# DAC_8CH.net
KiCad netlist of a schematic drawn in Altium Designer
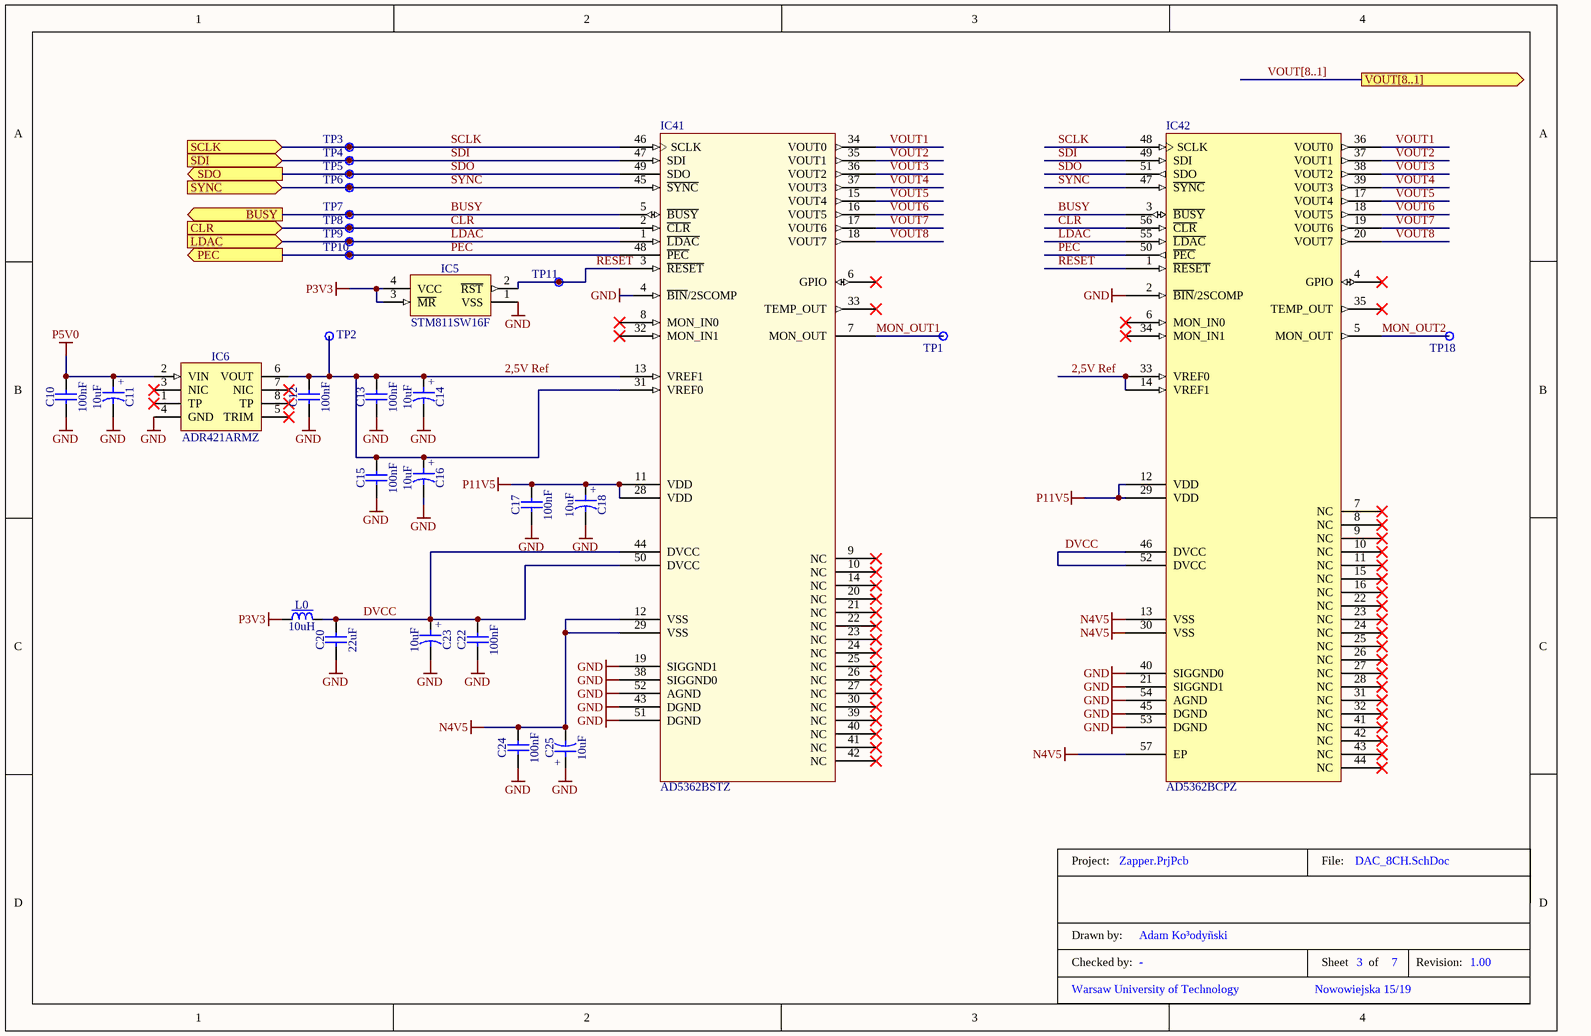
[diagram p0: DAC_8CH.SchDoc]

(export (version "E")
  (design (tool "Eeschema 10.0.6"))
  (components
    (comp (ref "C10")
      (value "100nF")
      (footprint "CAPC1005X55N")
      (description "Non-polarised capacitor")
      (fields
        (field (name "PART NUMBER") "CC0402_100NF_16V_10%_X7R")
        (field (name "VOLTAGE") "16V")
        (field (name "AUTHOR") "CERN DEM JLC")
      )
      (libsource (lib "Capacitors") (part "Capacitor - non polarized"))
    )
    (comp (ref "C11")
      (value "10uF")
      (footprint "CAPMP3528X210N")
      (description "Polarised capacitor")
      (fields
        (field (name "PART NUMBER") "CTE3528-21_10UF_16V_20%_PANASONIC_TQC")
        (field (name "VOLTAGE") "16V")
        (field (name "AUTHOR") "CERN DEM JLC")
      )
      (libsource (lib "Capacitors") (part "Capacitor - polarized"))
    )
    (comp (ref "C12")
      (value "100nF")
      (footprint "CAPC1005X55N")
      (description "Non-polarised capacitor")
      (fields
        (field (name "PART NUMBER") "CC0402_100NF_16V_10%_X7R")
        (field (name "VOLTAGE") "16V")
        (field (name "AUTHOR") "CERN DEM JLC")
      )
      (libsource (lib "Capacitors") (part "Capacitor - non polarized"))
    )
    (comp (ref "C13")
      (value "100nF")
      (footprint "CAPC1005X55N")
      (description "Non-polarised capacitor")
      (fields
        (field (name "PART NUMBER") "CC0402_100NF_16V_10%_X7R")
        (field (name "VOLTAGE") "16V")
        (field (name "AUTHOR") "CERN DEM JLC")
      )
      (libsource (lib "Capacitors") (part "Capacitor - non polarized"))
    )
    (comp (ref "C14")
      (value "10uF")
      (footprint "CAPMP3528X210N")
      (description "Polarised capacitor")
      (fields
        (field (name "PART NUMBER") "CTE3528-21_10UF_16V_20%_PANASONIC_TQC")
        (field (name "VOLTAGE") "16V")
        (field (name "AUTHOR") "CERN DEM JLC")
      )
      (libsource (lib "Capacitors") (part "Capacitor - polarized"))
    )
    (comp (ref "C15")
      (value "100nF")
      (footprint "CAPC1005X55N")
      (description "Non-polarised capacitor")
      (fields
        (field (name "PART NUMBER") "CC0402_100NF_16V_10%_X7R")
        (field (name "VOLTAGE") "16V")
        (field (name "AUTHOR") "CERN DEM JLC")
      )
      (libsource (lib "Capacitors") (part "Capacitor - non polarized"))
    )
    (comp (ref "C16")
      (value "10uF")
      (footprint "CAPMP3528X210N")
      (description "Polarised capacitor")
      (fields
        (field (name "PART NUMBER") "CTE3528-21_10UF_16V_20%_PANASONIC_TQC")
        (field (name "VOLTAGE") "16V")
        (field (name "AUTHOR") "CERN DEM JLC")
      )
      (libsource (lib "Capacitors") (part "Capacitor - polarized"))
    )
    (comp (ref "C17")
      (value "100nF")
      (footprint "CAPC1005X55N")
      (description "Non-polarised capacitor")
      (fields
        (field (name "PART NUMBER") "CC0402_100NF_16V_10%_X7R")
        (field (name "VOLTAGE") "16V")
        (field (name "AUTHOR") "CERN DEM JLC")
      )
      (libsource (lib "Capacitors") (part "Capacitor - non polarized"))
    )
    (comp (ref "C18")
      (value "10uF")
      (footprint "CAPMP3528X210N")
      (description "Polarised capacitor")
      (fields
        (field (name "PART NUMBER") "CTE3528-21_10UF_16V_20%_PANASONIC_TQC")
        (field (name "VOLTAGE") "16V")
        (field (name "AUTHOR") "CERN DEM JLC")
      )
      (libsource (lib "Capacitors") (part "Capacitor - polarized"))
    )
    (comp (ref "C20")
      (value "22uF")
      (footprint "CAPC2012X135N")
      (description "Non-polarised capacitor")
      (fields
        (field (name "PART NUMBER") "CC0805_22UF_16V_10%_X5R")
        (field (name "VOLTAGE") "16V")
        (field (name "AUTHOR") "CERN DEM JLC")
      )
      (libsource (lib "Capacitors") (part "Capacitor - non polarized"))
    )
    (comp (ref "C22")
      (value "100nF")
      (footprint "CAPC1005X55N")
      (description "Non-polarised capacitor")
      (fields
        (field (name "PART NUMBER") "CC0402_100NF_16V_10%_X7R")
        (field (name "VOLTAGE") "16V")
        (field (name "AUTHOR") "CERN DEM JLC")
      )
      (libsource (lib "Capacitors") (part "Capacitor - non polarized"))
    )
    (comp (ref "C23")
      (value "10uF")
      (footprint "CAPMP3528X210N")
      (description "Polarised capacitor")
      (fields
        (field (name "PART NUMBER") "CTE3528-21_10UF_16V_20%_PANASONIC_TQC")
        (field (name "VOLTAGE") "16V")
        (field (name "AUTHOR") "CERN DEM JLC")
      )
      (libsource (lib "Capacitors") (part "Capacitor - polarized"))
    )
    (comp (ref "C24")
      (value "100nF")
      (footprint "CAPC1005X55N")
      (description "Non-polarised capacitor")
      (fields
        (field (name "PART NUMBER") "CC0402_100NF_16V_10%_X7R")
        (field (name "VOLTAGE") "16V")
        (field (name "AUTHOR") "CERN DEM JLC")
      )
      (libsource (lib "Capacitors") (part "Capacitor - non polarized"))
    )
    (comp (ref "C25")
      (value "10uF")
      (footprint "CAPMP3528X210N")
      (description "Polarised capacitor")
      (fields
        (field (name "PART NUMBER") "CTE3528-21_10UF_16V_20%_PANASONIC_TQC")
        (field (name "VOLTAGE") "16V")
        (field (name "AUTHOR") "CERN DEM JLC")
      )
      (libsource (lib "Capacitors") (part "Capacitor - polarized"))
    )
    (comp (ref "IC5")
      (value "STM811SW16F")
      (footprint "SOT143N")
      (description "Microprocessor Reset Circuit")
      (fields (field (name "MANUFACTURER") "ST MICROELECTRONICS") (field (name "AUTHOR") "CERN DEM JLC"))
      (libsource (lib "ICs And Semiconductors") (part "STM811"))
    )
    (comp (ref "IC6")
      (value "ADR421ARMZ")
      (footprint "SOP65P490X110-8N")
      (description "Ultraprecision, Low Noise, 2.048 V/2.500 V/  3.00 V/5.00 V XFET Voltage References")
      (fields (field (name "MANUFACTURER") "ANALOG DEVICES") (field (name "AUTHOR") "CERN DEM JLC"))
      (libsource (lib "ICs And Semiconductors") (part "ADR42x"))
    )
    (comp (ref "IC41")
      (value "AD5362BSTZ")
      (footprint "ST-52_N")
      (description "IC, 16BIT DAC, 8CH, SERIAL, 52LFCSP")
      (libsource (lib "InzLib") (part "AD5362BSTZ"))
    )
    (comp (ref "IC42")
      (value "AD5362BCPZ")
      (footprint "CP-56-1_N")
      (description "DAC 8-CH Resistor-String 16-bit 56-Pin LFCSP EP Tray")
      (libsource (lib "InzLib") (part "AD5362BCPZ"))
    )
    (comp (ref "L0")
      (value "10uH")
      (footprint "IND_MURATA-PS_8400")
      (description "Inductor With Core")
      (fields
        (field (name "PART NUMBER") "IND_10UH_10%_MURATA-PS_8400")
        (field (name "POWER") "950mA")
        (field (name "AUTHOR") "CERN DEM JLC")
      )
      (libsource (lib "Inductors & Transformers") (part "Inductor With Magnetic core"))
    )
    (comp (ref "TitleBlock3") (value "TitleBlock") (libsource (lib "InzLib") (part "TitleBlock")))
    (comp (ref "TP1")
      (value "Test Point")
      (footprint "TPS127")
      (fields (field (name "PART NUMBER") "SMD_PAD_1.27X1.27MM") (field (name "AUTHOR") "CERN DEM JLC"))
      (libsource (lib "Eletro-mechanical") (part "Test Point"))
    )
    (comp (ref "TP2")
      (value "Test Point")
      (footprint "TPS127")
      (fields (field (name "PART NUMBER") "SMD_PAD_1.27X1.27MM") (field (name "AUTHOR") "CERN DEM JLC"))
      (libsource (lib "Eletro-mechanical") (part "Test Point"))
    )
    (comp (ref "TP3")
      (value "Test Point")
      (footprint "TPS127")
      (fields (field (name "PART NUMBER") "SMD_PAD_1.27X1.27MM") (field (name "AUTHOR") "CERN DEM JLC"))
      (libsource (lib "Eletro-mechanical") (part "Test Point"))
    )
    (comp (ref "TP4")
      (value "Test Point")
      (footprint "TPS127")
      (fields (field (name "PART NUMBER") "SMD_PAD_1.27X1.27MM") (field (name "AUTHOR") "CERN DEM JLC"))
      (libsource (lib "Eletro-mechanical") (part "Test Point"))
    )
    (comp (ref "TP5")
      (value "Test Point")
      (footprint "TPS127")
      (fields (field (name "PART NUMBER") "SMD_PAD_1.27X1.27MM") (field (name "AUTHOR") "CERN DEM JLC"))
      (libsource (lib "Eletro-mechanical") (part "Test Point"))
    )
    (comp (ref "TP6")
      (value "Test Point")
      (footprint "TPS127")
      (fields (field (name "PART NUMBER") "SMD_PAD_1.27X1.27MM") (field (name "AUTHOR") "CERN DEM JLC"))
      (libsource (lib "Eletro-mechanical") (part "Test Point"))
    )
    (comp (ref "TP7")
      (value "Test Point")
      (footprint "TPS127")
      (fields (field (name "PART NUMBER") "SMD_PAD_1.27X1.27MM") (field (name "AUTHOR") "CERN DEM JLC"))
      (libsource (lib "Eletro-mechanical") (part "Test Point"))
    )
    (comp (ref "TP8")
      (value "Test Point")
      (footprint "TPS127")
      (fields (field (name "PART NUMBER") "SMD_PAD_1.27X1.27MM") (field (name "AUTHOR") "CERN DEM JLC"))
      (libsource (lib "Eletro-mechanical") (part "Test Point"))
    )
    (comp (ref "TP9")
      (value "Test Point")
      (footprint "TPS127")
      (fields (field (name "PART NUMBER") "SMD_PAD_1.27X1.27MM") (field (name "AUTHOR") "CERN DEM JLC"))
      (libsource (lib "Eletro-mechanical") (part "Test Point"))
    )
    (comp (ref "TP10")
      (value "Test Point")
      (footprint "TPS127")
      (fields (field (name "PART NUMBER") "SMD_PAD_1.27X1.27MM") (field (name "AUTHOR") "CERN DEM JLC"))
      (libsource (lib "Eletro-mechanical") (part "Test Point"))
    )
    (comp (ref "TP11")
      (value "Test Point")
      (footprint "TPS127")
      (fields (field (name "PART NUMBER") "SMD_PAD_1.27X1.27MM") (field (name "AUTHOR") "CERN DEM JLC"))
      (libsource (lib "Eletro-mechanical") (part "Test Point"))
    )
    (comp (ref "TP18")
      (value "Test Point")
      (footprint "TPS127")
      (fields (field (name "PART NUMBER") "SMD_PAD_1.27X1.27MM") (field (name "AUTHOR") "CERN DEM JLC"))
      (libsource (lib "Eletro-mechanical") (part "Test Point"))
    )
  )
  (nets
    (net (code "1") (name "/2,5V Ref") (class "Default")
      (node (ref "C12") (pin "2") (pinfunction "2_2") (pintype "passive"))
      (node (ref "C13") (pin "2") (pinfunction "2_2") (pintype "passive"))
      (node (ref "C14") (pin "1") (pinfunction "1_1") (pintype "passive"))
      (node (ref "C15") (pin "2") (pinfunction "2_2") (pintype "passive"))
      (node (ref "C16") (pin "1") (pinfunction "1_1") (pintype "passive"))
      (node (ref "IC41") (pin "13") (pinfunction "VREF1_13") (pintype "input"))
      (node (ref "IC41") (pin "31") (pinfunction "VREF0_31") (pintype "input"))
      (node (ref "IC42") (pin "14") (pinfunction "VREF1_14") (pintype "input"))
      (node (ref "IC42") (pin "33") (pinfunction "VREF0_33") (pintype "input"))
      (node (ref "IC6") (pin "6") (pinfunction "VOUT_6") (pintype "power_in"))
      (node (ref "TP2") (pin "1") (pinfunction "1_1") (pintype "bidirectional"))
    )
    (net (code "2") (name "/BUSY") (class "Default")
      (node (ref "IC41") (pin "5") (pinfunction "~{BUSY}_5") (pintype "bidirectional"))
      (node (ref "IC42") (pin "3") (pinfunction "~{BUSY}_3") (pintype "bidirectional"))
      (node (ref "TP7") (pin "1") (pinfunction "1_1") (pintype "bidirectional"))
    )
    (net (code "3") (name "/CLR") (class "Default")
      (node (ref "IC41") (pin "2") (pinfunction "~{CLR}_2") (pintype "input"))
      (node (ref "IC42") (pin "56") (pinfunction "~{CLR}_56") (pintype "input"))
      (node (ref "TP8") (pin "1") (pinfunction "1_1") (pintype "bidirectional"))
    )
    (net (code "4") (name "/DVCC") (class "Default")
      (node (ref "C20") (pin "2") (pinfunction "2_2") (pintype "passive"))
      (node (ref "C22") (pin "2") (pinfunction "2_2") (pintype "passive"))
      (node (ref "C23") (pin "1") (pinfunction "1_1") (pintype "passive"))
      (node (ref "IC41") (pin "44") (pinfunction "DVCC_44") (pintype "power_in"))
      (node (ref "IC41") (pin "50") (pinfunction "DVCC_50") (pintype "power_in"))
      (node (ref "IC42") (pin "46") (pinfunction "DVCC_46") (pintype "passive"))
      (node (ref "IC42") (pin "52") (pinfunction "DVCC_52") (pintype "passive"))
      (node (ref "L0") (pin "2") (pinfunction "2_2") (pintype "passive"))
    )
    (net (code "5") (name "/LDAC") (class "Default")
      (node (ref "IC41") (pin "1") (pinfunction "~{LDAC}_1") (pintype "input"))
      (node (ref "IC42") (pin "55") (pinfunction "~{LDAC}_55") (pintype "input"))
      (node (ref "TP9") (pin "1") (pinfunction "1_1") (pintype "bidirectional"))
    )
    (net (code "6") (name "/MON_OUT1") (class "Default")
      (node (ref "IC41") (pin "7") (pinfunction "MON_OUT_7") (pintype "tri_state"))
      (node (ref "TP1") (pin "1") (pinfunction "1_1") (pintype "bidirectional"))
    )
    (net (code "7") (name "/MON_OUT2") (class "Default")
      (node (ref "IC42") (pin "5") (pinfunction "MON_OUT_5") (pintype "output"))
      (node (ref "TP18") (pin "1") (pinfunction "1_1") (pintype "bidirectional"))
    )
    (net (code "8") (name "/PEC") (class "Default")
      (node (ref "IC41") (pin "48") (pinfunction "~{PEC}_48") (pintype "open_collector"))
      (node (ref "IC42") (pin "50") (pinfunction "~{PEC}_50") (pintype "output"))
      (node (ref "TP10") (pin "1") (pinfunction "1_1") (pintype "bidirectional"))
    )
    (net (code "9") (name "/SCLK") (class "Default")
      (node (ref "IC41") (pin "46") (pinfunction "SCLK_46") (pintype "input"))
      (node (ref "IC42") (pin "48") (pinfunction "SCLK_48") (pintype "input"))
      (node (ref "TP3") (pin "1") (pinfunction "1_1") (pintype "bidirectional"))
    )
    (net (code "10") (name "/SDI") (class "Default")
      (node (ref "IC41") (pin "47") (pinfunction "SDI_47") (pintype "input"))
      (node (ref "IC42") (pin "49") (pinfunction "SDI_49") (pintype "input"))
      (node (ref "TP4") (pin "1") (pinfunction "1_1") (pintype "bidirectional"))
    )
    (net (code "11") (name "/SDO") (class "Default")
      (node (ref "IC41") (pin "49") (pinfunction "SDO_49") (pintype "tri_state"))
      (node (ref "IC42") (pin "51") (pinfunction "SDO_51") (pintype "output"))
      (node (ref "TP5") (pin "1") (pinfunction "1_1") (pintype "bidirectional"))
    )
    (net (code "12") (name "/SYNC") (class "Default")
      (node (ref "IC41") (pin "45") (pinfunction "~{SYNC}_45") (pintype "input"))
      (node (ref "IC42") (pin "47") (pinfunction "~{SYNC}_47") (pintype "input"))
      (node (ref "TP6") (pin "1") (pinfunction "1_1") (pintype "bidirectional"))
    )
    (net (code "13") (name "/VOUT1") (class "Default")
      (node (ref "IC41") (pin "34") (pinfunction "VOUT0_34") (pintype "output"))
      (node (ref "IC42") (pin "36") (pinfunction "VOUT0_36") (pintype "output"))
    )
    (net (code "14") (name "/VOUT2") (class "Default")
      (node (ref "IC41") (pin "35") (pinfunction "VOUT1_35") (pintype "output"))
      (node (ref "IC42") (pin "37") (pinfunction "VOUT1_37") (pintype "output"))
    )
    (net (code "15") (name "/VOUT3") (class "Default")
      (node (ref "IC41") (pin "36") (pinfunction "VOUT2_36") (pintype "output"))
      (node (ref "IC42") (pin "38") (pinfunction "VOUT2_38") (pintype "output"))
    )
    (net (code "16") (name "/VOUT4") (class "Default")
      (node (ref "IC41") (pin "37") (pinfunction "VOUT3_37") (pintype "output"))
      (node (ref "IC42") (pin "39") (pinfunction "VOUT3_39") (pintype "output"))
    )
    (net (code "17") (name "/VOUT5") (class "Default")
      (node (ref "IC41") (pin "15") (pinfunction "VOUT4_15") (pintype "output"))
      (node (ref "IC42") (pin "17") (pinfunction "VOUT4_17") (pintype "output"))
    )
    (net (code "18") (name "/VOUT6") (class "Default")
      (node (ref "IC41") (pin "16") (pinfunction "VOUT5_16") (pintype "output"))
      (node (ref "IC42") (pin "18") (pinfunction "VOUT5_18") (pintype "output"))
    )
    (net (code "19") (name "/VOUT7") (class "Default")
      (node (ref "IC41") (pin "17") (pinfunction "VOUT6_17") (pintype "output"))
      (node (ref "IC42") (pin "19") (pinfunction "VOUT6_19") (pintype "output"))
    )
    (net (code "20") (name "/VOUT8") (class "Default")
      (node (ref "IC41") (pin "18") (pinfunction "VOUT7_18") (pintype "output"))
      (node (ref "IC42") (pin "20") (pinfunction "VOUT7_20") (pintype "output"))
    )
    (net (code "22") (name "/~{RESET}") (class "Default")
      (node (ref "IC41") (pin "3") (pinfunction "~{RESET}_3") (pintype "input"))
      (node (ref "IC42") (pin "1") (pinfunction "~{RESET}_1") (pintype "input"))
      (node (ref "IC5") (pin "2") (pinfunction "~{RST}_2") (pintype "output"))
      (node (ref "TP11") (pin "1") (pinfunction "1_1") (pintype "bidirectional"))
    )
    (net (code "23") (name "GND") (class "Default")
      (node (ref "C10") (pin "1") (pinfunction "1_1") (pintype "passive"))
      (node (ref "C11") (pin "2") (pinfunction "2_2") (pintype "passive"))
      (node (ref "C12") (pin "1") (pinfunction "1_1") (pintype "passive"))
      (node (ref "C13") (pin "1") (pinfunction "1_1") (pintype "passive"))
      (node (ref "C14") (pin "2") (pinfunction "2_2") (pintype "passive"))
      (node (ref "C15") (pin "1") (pinfunction "1_1") (pintype "passive"))
      (node (ref "C16") (pin "2") (pinfunction "2_2") (pintype "passive"))
      (node (ref "C17") (pin "1") (pinfunction "1_1") (pintype "passive"))
      (node (ref "C18") (pin "2") (pinfunction "2_2") (pintype "passive"))
      (node (ref "C20") (pin "1") (pinfunction "1_1") (pintype "passive"))
      (node (ref "C22") (pin "1") (pinfunction "1_1") (pintype "passive"))
      (node (ref "C23") (pin "2") (pinfunction "2_2") (pintype "passive"))
      (node (ref "C24") (pin "1") (pinfunction "1_1") (pintype "passive"))
      (node (ref "C25") (pin "1") (pinfunction "1_1") (pintype "passive"))
      (node (ref "IC41") (pin "19") (pinfunction "SIGGND1_19") (pintype "power_in"))
      (node (ref "IC41") (pin "38") (pinfunction "SIGGND0_38") (pintype "power_in"))
      (node (ref "IC41") (pin "4") (pinfunction "~{BIN}/2SCOMP_4") (pintype "input"))
      (node (ref "IC41") (pin "43") (pinfunction "DGND_43") (pintype "power_in"))
      (node (ref "IC41") (pin "51") (pinfunction "DGND_51") (pintype "power_in"))
      (node (ref "IC41") (pin "52") (pinfunction "AGND_52") (pintype "power_in"))
      (node (ref "IC42") (pin "2") (pinfunction "~{BIN}/2SCOMP_2") (pintype "input"))
      (node (ref "IC42") (pin "21") (pinfunction "SIGGND1_21") (pintype "passive"))
      (node (ref "IC42") (pin "40") (pinfunction "SIGGND0_40") (pintype "passive"))
      (node (ref "IC42") (pin "45") (pinfunction "DGND_45") (pintype "passive"))
      (node (ref "IC42") (pin "53") (pinfunction "DGND_53") (pintype "passive"))
      (node (ref "IC42") (pin "54") (pinfunction "AGND_54") (pintype "passive"))
      (node (ref "IC5") (pin "1") (pinfunction "VSS_1") (pintype "power_in"))
      (node (ref "IC6") (pin "4") (pinfunction "GND_4") (pintype "power_in"))
    )
    (net (code "24") (name "N4V5") (class "Default")
      (node (ref "C24") (pin "2") (pinfunction "2_2") (pintype "passive"))
      (node (ref "C25") (pin "2") (pinfunction "2_2") (pintype "passive"))
      (node (ref "IC41") (pin "12") (pinfunction "VSS_12") (pintype "power_in"))
      (node (ref "IC41") (pin "29") (pinfunction "VSS_29") (pintype "power_in"))
      (node (ref "IC42") (pin "13") (pinfunction "VSS_13") (pintype "passive"))
      (node (ref "IC42") (pin "30") (pinfunction "VSS_30") (pintype "passive"))
      (node (ref "IC42") (pin "57") (pinfunction "EP_57") (pintype "passive"))
    )
    (net (code "25") (name "P3V3") (class "Default")
      (node (ref "IC5") (pin "3") (pinfunction "~{MR}_3") (pintype "input"))
      (node (ref "IC5") (pin "4") (pinfunction "VCC_4") (pintype "power_in"))
      (node (ref "L0") (pin "1") (pinfunction "1_1") (pintype "passive"))
    )
    (net (code "26") (name "P5V0") (class "Default")
      (node (ref "C10") (pin "2") (pinfunction "2_2") (pintype "passive"))
      (node (ref "C11") (pin "1") (pinfunction "1_1") (pintype "passive"))
      (node (ref "IC6") (pin "2") (pinfunction "VIN_2") (pintype "input"))
    )
    (net (code "27") (name "P11V5") (class "Default")
      (node (ref "C17") (pin "2") (pinfunction "2_2") (pintype "passive"))
      (node (ref "C18") (pin "1") (pinfunction "1_1") (pintype "passive"))
      (node (ref "IC41") (pin "11") (pinfunction "VDD_11") (pintype "power_in"))
      (node (ref "IC41") (pin "28") (pinfunction "VDD_28") (pintype "power_in"))
      (node (ref "IC42") (pin "12") (pinfunction "VDD_12") (pintype "passive"))
      (node (ref "IC42") (pin "29") (pinfunction "VDD_29") (pintype "passive"))
    )
    (net (code "28") (name "unconnected-(IC6-NIC-Pad3)") (class "Default")
      (node (ref "IC6") (pin "3") (pinfunction "NIC_3") (pintype "passive+no_connect"))
    )
    (net (code "29") (name "unconnected-(IC6-NIC-Pad7)") (class "Default")
      (node (ref "IC6") (pin "7") (pinfunction "NIC_7") (pintype "passive+no_connect"))
    )
    (net (code "30") (name "unconnected-(IC6-TP-Pad1)") (class "Default")
      (node (ref "IC6") (pin "1") (pinfunction "TP_1") (pintype "passive+no_connect"))
    )
    (net (code "31") (name "unconnected-(IC6-TP-Pad8)") (class "Default")
      (node (ref "IC6") (pin "8") (pinfunction "TP_8") (pintype "passive+no_connect"))
    )
    (net (code "32") (name "unconnected-(IC6-TRIM-Pad5)") (class "Default")
      (node (ref "IC6") (pin "5") (pinfunction "TRIM_5") (pintype "passive+no_connect"))
    )
    (net (code "33") (name "unconnected-(IC41-GPIO-Pad6)") (class "Default")
      (node (ref "IC41") (pin "6") (pinfunction "GPIO_6") (pintype "bidirectional+no_connect"))
    )
    (net (code "34") (name "unconnected-(IC41-MON_IN0-Pad8)") (class "Default")
      (node (ref "IC41") (pin "8") (pinfunction "MON_IN0_8") (pintype "input+no_connect"))
    )
    (net (code "35") (name "unconnected-(IC41-MON_IN1-Pad32)") (class "Default")
      (node (ref "IC41") (pin "32") (pinfunction "MON_IN1_32") (pintype "input+no_connect"))
    )
    (net (code "36") (name "unconnected-(IC41-NC-Pad9)") (class "Default")
      (node (ref "IC41") (pin "9") (pinfunction "NC_9") (pintype "passive+no_connect"))
    )
    (net (code "37") (name "unconnected-(IC41-NC-Pad10)") (class "Default")
      (node (ref "IC41") (pin "10") (pinfunction "NC_10") (pintype "passive+no_connect"))
    )
    (net (code "38") (name "unconnected-(IC41-NC-Pad14)") (class "Default")
      (node (ref "IC41") (pin "14") (pinfunction "NC_14") (pintype "passive+no_connect"))
    )
    (net (code "39") (name "unconnected-(IC41-NC-Pad20)") (class "Default")
      (node (ref "IC41") (pin "20") (pinfunction "NC_20") (pintype "passive+no_connect"))
    )
    (net (code "40") (name "unconnected-(IC41-NC-Pad21)") (class "Default")
      (node (ref "IC41") (pin "21") (pinfunction "NC_21") (pintype "passive+no_connect"))
    )
    (net (code "41") (name "unconnected-(IC41-NC-Pad22)") (class "Default")
      (node (ref "IC41") (pin "22") (pinfunction "NC_22") (pintype "passive+no_connect"))
    )
    (net (code "42") (name "unconnected-(IC41-NC-Pad23)") (class "Default")
      (node (ref "IC41") (pin "23") (pinfunction "NC_23") (pintype "passive+no_connect"))
    )
    (net (code "43") (name "unconnected-(IC41-NC-Pad24)") (class "Default")
      (node (ref "IC41") (pin "24") (pinfunction "NC_24") (pintype "passive+no_connect"))
    )
    (net (code "44") (name "unconnected-(IC41-NC-Pad25)") (class "Default")
      (node (ref "IC41") (pin "25") (pinfunction "NC_25") (pintype "passive+no_connect"))
    )
    (net (code "45") (name "unconnected-(IC41-NC-Pad26)") (class "Default")
      (node (ref "IC41") (pin "26") (pinfunction "NC_26") (pintype "passive+no_connect"))
    )
    (net (code "46") (name "unconnected-(IC41-NC-Pad27)") (class "Default")
      (node (ref "IC41") (pin "27") (pinfunction "NC_27") (pintype "passive+no_connect"))
    )
    (net (code "47") (name "unconnected-(IC41-NC-Pad30)") (class "Default")
      (node (ref "IC41") (pin "30") (pinfunction "NC_30") (pintype "passive+no_connect"))
    )
    (net (code "48") (name "unconnected-(IC41-NC-Pad39)") (class "Default")
      (node (ref "IC41") (pin "39") (pinfunction "NC_39") (pintype "passive+no_connect"))
    )
    (net (code "49") (name "unconnected-(IC41-NC-Pad40)") (class "Default")
      (node (ref "IC41") (pin "40") (pinfunction "NC_40") (pintype "passive+no_connect"))
    )
    (net (code "50") (name "unconnected-(IC41-NC-Pad41)") (class "Default")
      (node (ref "IC41") (pin "41") (pinfunction "NC_41") (pintype "passive+no_connect"))
    )
    (net (code "51") (name "unconnected-(IC41-NC-Pad42)") (class "Default")
      (node (ref "IC41") (pin "42") (pinfunction "NC_42") (pintype "passive+no_connect"))
    )
    (net (code "52") (name "unconnected-(IC41-TEMP_OUT-Pad33)") (class "Default")
      (node (ref "IC41") (pin "33") (pinfunction "TEMP_OUT_33") (pintype "output+no_connect"))
    )
    (net (code "53") (name "unconnected-(IC42-GPIO-Pad4)") (class "Default")
      (node (ref "IC42") (pin "4") (pinfunction "GPIO_4") (pintype "bidirectional+no_connect"))
    )
    (net (code "54") (name "unconnected-(IC42-MON_IN0-Pad6)") (class "Default")
      (node (ref "IC42") (pin "6") (pinfunction "MON_IN0_6") (pintype "input+no_connect"))
    )
    (net (code "55") (name "unconnected-(IC42-MON_IN1-Pad34)") (class "Default")
      (node (ref "IC42") (pin "34") (pinfunction "MON_IN1_34") (pintype "input+no_connect"))
    )
    (net (code "56") (name "unconnected-(IC42-NC-Pad7)") (class "Default")
      (node (ref "IC42") (pin "7") (pinfunction "NC_7") (pintype "passive+no_connect"))
    )
    (net (code "57") (name "unconnected-(IC42-NC-Pad8)") (class "Default")
      (node (ref "IC42") (pin "8") (pinfunction "NC_8") (pintype "passive+no_connect"))
    )
    (net (code "58") (name "unconnected-(IC42-NC-Pad9)") (class "Default")
      (node (ref "IC42") (pin "9") (pinfunction "NC_9") (pintype "passive+no_connect"))
    )
    (net (code "59") (name "unconnected-(IC42-NC-Pad10)") (class "Default")
      (node (ref "IC42") (pin "10") (pinfunction "NC_10") (pintype "passive+no_connect"))
    )
    (net (code "60") (name "unconnected-(IC42-NC-Pad11)") (class "Default")
      (node (ref "IC42") (pin "11") (pinfunction "NC_11") (pintype "passive+no_connect"))
    )
    (net (code "61") (name "unconnected-(IC42-NC-Pad15)") (class "Default")
      (node (ref "IC42") (pin "15") (pinfunction "NC_15") (pintype "passive+no_connect"))
    )
    (net (code "62") (name "unconnected-(IC42-NC-Pad16)") (class "Default")
      (node (ref "IC42") (pin "16") (pinfunction "NC_16") (pintype "passive+no_connect"))
    )
    (net (code "63") (name "unconnected-(IC42-NC-Pad22)") (class "Default")
      (node (ref "IC42") (pin "22") (pinfunction "NC_22") (pintype "passive+no_connect"))
    )
    (net (code "64") (name "unconnected-(IC42-NC-Pad23)") (class "Default")
      (node (ref "IC42") (pin "23") (pinfunction "NC_23") (pintype "passive+no_connect"))
    )
    (net (code "65") (name "unconnected-(IC42-NC-Pad24)") (class "Default")
      (node (ref "IC42") (pin "24") (pinfunction "NC_24") (pintype "passive+no_connect"))
    )
    (net (code "66") (name "unconnected-(IC42-NC-Pad25)") (class "Default")
      (node (ref "IC42") (pin "25") (pinfunction "NC_25") (pintype "passive+no_connect"))
    )
    (net (code "67") (name "unconnected-(IC42-NC-Pad26)") (class "Default")
      (node (ref "IC42") (pin "26") (pinfunction "NC_26") (pintype "passive+no_connect"))
    )
    (net (code "68") (name "unconnected-(IC42-NC-Pad27)") (class "Default")
      (node (ref "IC42") (pin "27") (pinfunction "NC_27") (pintype "passive+no_connect"))
    )
    (net (code "69") (name "unconnected-(IC42-NC-Pad28)") (class "Default")
      (node (ref "IC42") (pin "28") (pinfunction "NC_28") (pintype "passive+no_connect"))
    )
    (net (code "70") (name "unconnected-(IC42-NC-Pad31)") (class "Default")
      (node (ref "IC42") (pin "31") (pinfunction "NC_31") (pintype "passive+no_connect"))
    )
    (net (code "71") (name "unconnected-(IC42-NC-Pad32)") (class "Default")
      (node (ref "IC42") (pin "32") (pinfunction "NC_32") (pintype "passive+no_connect"))
    )
    (net (code "72") (name "unconnected-(IC42-NC-Pad41)") (class "Default")
      (node (ref "IC42") (pin "41") (pinfunction "NC_41") (pintype "passive+no_connect"))
    )
    (net (code "73") (name "unconnected-(IC42-NC-Pad42)") (class "Default")
      (node (ref "IC42") (pin "42") (pinfunction "NC_42") (pintype "passive+no_connect"))
    )
    (net (code "74") (name "unconnected-(IC42-NC-Pad43)") (class "Default")
      (node (ref "IC42") (pin "43") (pinfunction "NC_43") (pintype "passive+no_connect"))
    )
    (net (code "75") (name "unconnected-(IC42-NC-Pad44)") (class "Default")
      (node (ref "IC42") (pin "44") (pinfunction "NC_44") (pintype "passive+no_connect"))
    )
    (net (code "76") (name "unconnected-(IC42-TEMP_OUT-Pad35)") (class "Default")
      (node (ref "IC42") (pin "35") (pinfunction "TEMP_OUT_35") (pintype "output+no_connect"))
    )
  )
)
